# bt_rc_car_vehicle.net
KiCad netlist of a schematic drawn in EAGLE
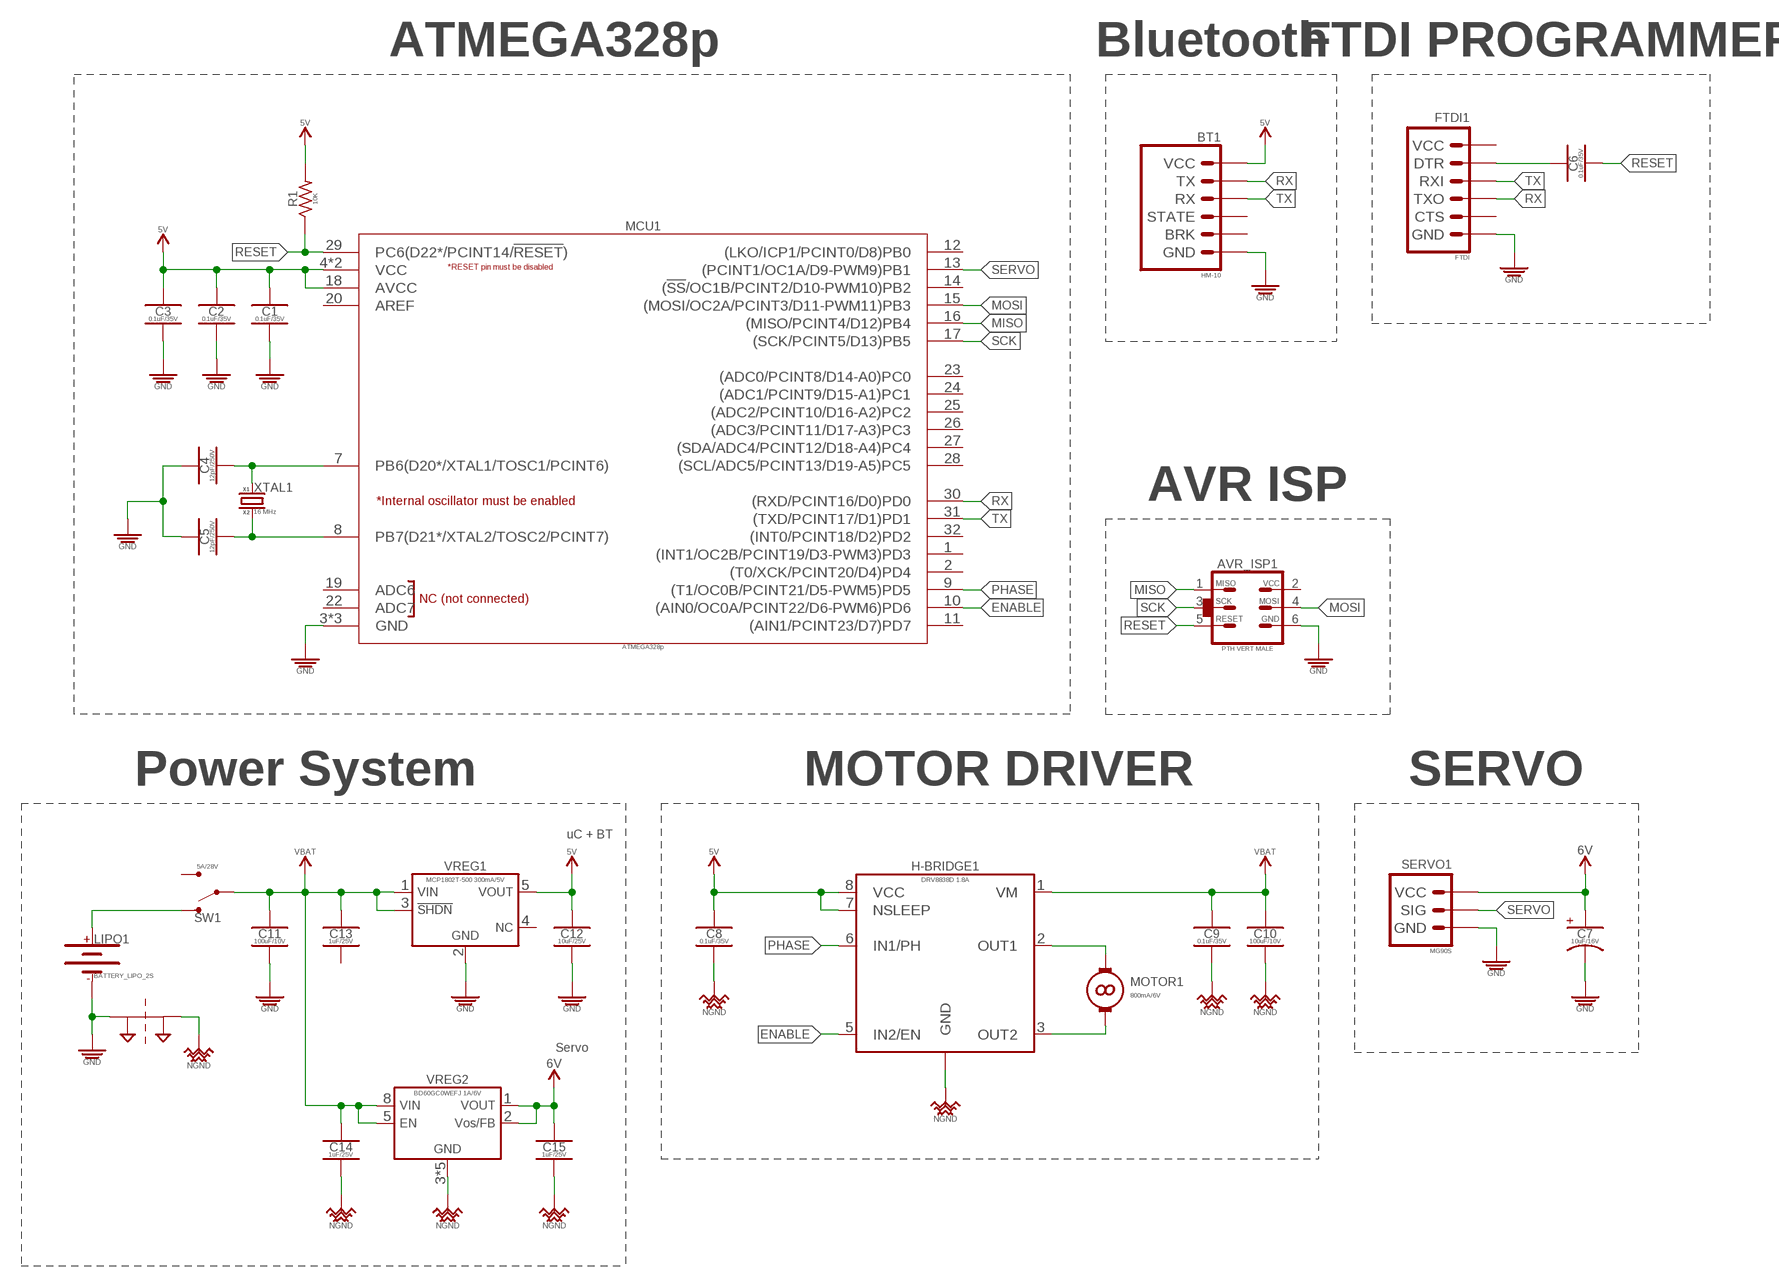
[diagram p0: schematic, sheet 1]

(export (version "E")
  (design (tool "Eeschema 10.0.6"))
  (components
    (comp (ref "AVR_ISP1")
      (value "PTH VERT MALE")
      (footprint "eagle-import:HDRV6W64P254_2X3_762X483X838B_AVR-ISP")
      (fields (field (name "MFR") "Amphenol FCI") (field (name "MPN") "67997-206HLF"))
      (libsource (lib "eagle-import") (part "AVR_SPI_PRG_6_PTH_VERT_MALE_2.54MM"))
    )
    (comp (ref "BT1")
      (value "HM-10")
      (footprint "eagle-import:HDRVR6W64P254_1X6_1574X254X850B")
      (fields (field (name "MFR") "JNHuaMao Technology Company"))
      (libsource (lib "eagle-import") (part "BLUETOOTH_HM-10_PTH_VERT_FEMALE_2.54MM"))
    )
    (comp (ref "C1")
      (value "0.1uF/35V")
      (footprint "eagle-import:CAPC2012X95_SMD-0805")
      (fields (field (name "MFR") "Taiyo Yuden") (field (name "MPN") "GMK212BJ104KGHT"))
      (libsource (lib "eagle-import") (part "0.1UF_SMD-0805_35V-10%"))
    )
    (comp (ref "C2")
      (value "0.1uF/35V")
      (footprint "eagle-import:CAPC2012X95_SMD-0805")
      (fields (field (name "MFR") "Taiyo Yuden") (field (name "MPN") "GMK212BJ104KGHT"))
      (libsource (lib "eagle-import") (part "0.1UF_SMD-0805_35V-10%"))
    )
    (comp (ref "C3")
      (value "0.1uF/35V")
      (footprint "eagle-import:CAPC2012X95_SMD-0805")
      (fields (field (name "MFR") "Taiyo Yuden") (field (name "MPN") "GMK212BJ104KGHT"))
      (libsource (lib "eagle-import") (part "0.1UF_SMD-0805_35V-10%"))
    )
    (comp (ref "C4")
      (value "12pF/250V")
      (footprint "eagle-import:CAPC2012X95_SMD-0805")
      (fields
        (field (name "MFR") "Murata Electronics North America")
        (field (name "MPN") "GRM21A5C2E120JW01D")
      )
      (libsource (lib "eagle-import") (part "12PF_SMD-0805_250V-5%"))
    )
    (comp (ref "C5")
      (value "12pF/250V")
      (footprint "eagle-import:CAPC2012X95_SMD-0805")
      (fields
        (field (name "MFR") "Murata Electronics North America")
        (field (name "MPN") "GRM21A5C2E120JW01D")
      )
      (libsource (lib "eagle-import") (part "12PF_SMD-0805_250V-5%"))
    )
    (comp (ref "C6")
      (value "0.1uF/35V")
      (footprint "eagle-import:CAPC2012X95_SMD-0805")
      (fields (field (name "MFR") "Taiyo Yuden") (field (name "MPN") "GMK212BJ104KGHT"))
      (libsource (lib "eagle-import") (part "0.1UF_SMD-0805_35V-10%"))
    )
    (comp (ref "C7")
      (value "10uF/16V")
      (footprint "eagle-import:CAPMP3216X180_SMD_CAP-TANT-1206")
      (fields (field (name "MFR") "TCJA106M016R0200"))
      (libsource (lib "eagle-import") (part "10UF-POLARIZED_SMD-1206_16V-20%_"))
    )
    (comp (ref "C8")
      (value "0.1uF/35V")
      (footprint "eagle-import:CAPC2012X95_SMD-0805")
      (fields (field (name "MFR") "Taiyo Yuden") (field (name "MPN") "GMK212BJ104KGHT"))
      (libsource (lib "eagle-import") (part "0.1UF_SMD-0805_35V-10%"))
    )
    (comp (ref "C9")
      (value "0.1uF/35V")
      (footprint "eagle-import:CAPC2012X95_SMD-0805")
      (fields (field (name "MFR") "Taiyo Yuden") (field (name "MPN") "GMK212BJ104KGHT"))
      (libsource (lib "eagle-import") (part "0.1UF_SMD-0805_35V-10%"))
    )
    (comp (ref "C10")
      (value "100uF/10V")
      (footprint "eagle-import:CAPC3225X270_SMD-1210")
      (fields (field (name "MFR") "Taiyo Yuden") (field (name "MPN") "LMK325ABJ107MMHT"))
      (libsource (lib "eagle-import") (part "100UF_CER_SMD-1210_16V-20%"))
    )
    (comp (ref "C11")
      (value "100uF/10V")
      (footprint "eagle-import:CAPC3225X270_SMD-1210")
      (fields (field (name "MFR") "Taiyo Yuden") (field (name "MPN") "LMK325ABJ107MMHT"))
      (libsource (lib "eagle-import") (part "100UF_CER_SMD-1210_16V-20%"))
    )
    (comp (ref "C12")
      (value "10uF/25V")
      (footprint "eagle-import:CAPC2012X95_SMD-0805")
      (fields
        (field (name "MFR") "Murata Electronics North America")
        (field (name "MPN") "GRM21BR61E106MA73L")
      )
      (libsource (lib "eagle-import") (part "10UF_CER_SMD-0805_25V-10%"))
    )
    (comp (ref "C13")
      (value "1uF/25V")
      (footprint "eagle-import:CAPC2012X95_SMD-0805")
      (fields (field (name "MFR") "KEMET") (field (name "MPN") "C0805C105K3RACTU"))
      (libsource (lib "eagle-import") (part "1UF_CER_SMD-0805_25V-10%"))
    )
    (comp (ref "C14")
      (value "1uF/25V")
      (footprint "eagle-import:CAPC2012X95_SMD-0805")
      (fields (field (name "MFR") "KEMET") (field (name "MPN") "C0805C105K3RACTU"))
      (libsource (lib "eagle-import") (part "1UF_CER_SMD-0805_25V-10%"))
    )
    (comp (ref "C15")
      (value "1uF/25V")
      (footprint "eagle-import:CAPC2012X95_SMD-0805")
      (fields (field (name "MFR") "KEMET") (field (name "MPN") "C0805C105K3RACTU"))
      (libsource (lib "eagle-import") (part "1UF_CER_SMD-0805_25V-10%"))
    )
    (comp (ref "FTDI1")
      (value "FTDI")
      (footprint "eagle-import:HDRV6W64P254_1X6_1524X254X838B_FTDI")
      (fields (field (name "MFR") "SparkFun Electronics") (field (name "MPN") "DEV-09873"))
      (libsource (lib "eagle-import") (part "FTDI_PTH_VERT_MALE_2.54MM"))
    )
    (comp (ref "H-BRIDGE1")
      (value "DRV8838D 1.8A")
      (footprint "eagle-import:WSON-8-PPAD")
      (fields (field (name "MFR") "Texas Instruments") (field (name "MPN") "DRV8838DSGR"))
      (libsource (lib "eagle-import") (part "DRV883X_H-BRIDGE_DRV8838D_1.8A"))
    )
    (comp (ref "LIPO1")
      (value "BATTERY_LIPO_2S")
      (footprint "eagle-import:DUAL_PTH_PADS")
      (libsource (lib "eagle-import") (part "BATTERY_LIPO_2S"))
    )
    (comp (ref "MCU1")
      (value "ATMEGA328p")
      (footprint "eagle-import:QFP80P900X900X120-32")
      (fields (field (name "MFR") "Microchip Technology") (field (name "MPN") "ATMEGA328P-AU"))
      (libsource (lib "eagle-import") (part "ATMEGA328P-32_TQFP-32_ATMEGA328P"))
    )
    (comp (ref "MOTOR1")
      (value "800mA/6V")
      (footprint "eagle-import:CONNECTOR_MOTOR")
      (fields (field (name "MFR") "Pololu") (field (name "MPN") "1117"))
      (libsource (lib "eagle-import") (part "MOTOR_SIZE-130"))
    )
    (comp (ref "NET_BRIDGE1")
      (value "NET_BRIDGE")
      (footprint "eagle-import:NET_BRIDGE")
      (libsource (lib "eagle-import") (part "NET_BRIDGE"))
    )
    (comp (ref "R1")
      (value "10K")
      (footprint "eagle-import:RESC2012X60_SMD-0805")
      (fields (field (name "MFR") "Yageo") (field (name "MPN") "RC0805JR-0710KL"))
      (libsource (lib "eagle-import") (part "10KΩ_SMD-0805_1/8W-5%"))
    )
    (comp (ref "SERVO1")
      (value "MG90S")
      (footprint "eagle-import:HDRV3W64P254_1X3_762X254X838B")
      (fields (field (name "MFR") "TowerPro"))
      (libsource (lib "eagle-import") (part "SERVO_MG90S_PTH_VERT_MALE_2.54MM"))
    )
    (comp (ref "SW1")
      (value "5A/28V")
      (footprint "eagle-import:SW_TOGGLE_SPDT_5A-28V_13L-7W")
      (fields (field (name "MFR") "E-Switch") (field (name "MPN") "100SP1T1B4M2QE"))
      (libsource (lib "eagle-import") (part "SWITCH_SPDT_VERT_PTH_5A-28V_13L-7W_"))
    )
    (comp (ref "VREG1")
      (value "MCP1802T-500 300mA/5V")
      (footprint "eagle-import:SOT95P280X145-5")
      (fields (field (name "MFR") "Microchip Technology") (field (name "MPN") "MCP1802T-5002I/OT"))
      (libsource (lib "eagle-import") (part "MCP18XX_MCP1802-500_300MA-5V"))
    )
    (comp (ref "VREG2")
      (value "BD60GC0WEFJ 1A/6V")
      (footprint "eagle-import:SOIC127P600X100-8")
      (fields (field (name "MFR") "Rohm Semiconductor") (field (name "MPN") "BD60GC0WEFJ-E2"))
      (libsource (lib "eagle-import") (part "BDXXGC0WEFJ_BD60GC0WEFJ_1A-6V"))
    )
    (comp (ref "XTAL1")
      (value "16 MHz")
      (footprint "eagle-import:OSCCC500X320X110_CRYSTAL")
      (fields (field (name "MFR") "Abracon LLC") (field (name "MPN") "ABM3B-16.000MHZ-B2-T"))
      (libsource (lib "eagle-import") (part "CRYSTAL_ABM3B_16MHZ_18PF"))
    )
  )
  (nets
    (net (code "1") (name "5V") (class "Default")
      (node (ref "BT1") (pin "VCC") (pinfunction "VCC_VCC") (pintype "passive"))
      (node (ref "C1") (pin "1") (pinfunction "1_1") (pintype "passive"))
      (node (ref "C12") (pin "1") (pinfunction "1_1") (pintype "passive"))
      (node (ref "C2") (pin "1") (pinfunction "1_1") (pintype "passive"))
      (node (ref "C3") (pin "1") (pinfunction "1_1") (pintype "passive"))
      (node (ref "C8") (pin "1") (pinfunction "1_1") (pintype "passive"))
      (node (ref "H-BRIDGE1") (pin "7") (pinfunction "NSLEEP_7") (pintype "passive"))
      (node (ref "H-BRIDGE1") (pin "8") (pinfunction "VCC_8") (pintype "passive"))
      (node (ref "MCU1") (pin "18") (pinfunction "AVCC_18") (pintype "power_in"))
      (node (ref "MCU1") (pin "4") (pinfunction "VCC_4") (pintype "power_in"))
      (node (ref "MCU1") (pin "6") (pinfunction "VCC_6") (pintype "power_in"))
      (node (ref "R1") (pin "2") (pinfunction "2_2") (pintype "passive"))
      (node (ref "VREG1") (pin "5") (pinfunction "VOUT_5") (pintype "passive"))
    )
    (net (code "2") (name "6V") (class "Default")
      (node (ref "C15") (pin "1") (pinfunction "1_1") (pintype "passive"))
      (node (ref "C7") (pin "A") (pinfunction "A_A") (pintype "passive"))
      (node (ref "SERVO1") (pin "VCC") (pinfunction "VCC_VCC") (pintype "passive"))
      (node (ref "VREG2") (pin "1") (pinfunction "VOUT_1") (pintype "bidirectional"))
      (node (ref "VREG2") (pin "2") (pinfunction "VOS/FB_2") (pintype "bidirectional"))
    )
    (net (code "3") (name "ENABLE") (class "Default")
      (node (ref "H-BRIDGE1") (pin "5") (pinfunction "IN2/EN_5") (pintype "input"))
      (node (ref "MCU1") (pin "10") (pinfunction "(AIN0/OC0A/PCINT22/D6-PWM6)PD6_10") (pintype "bidirectional"))
    )
    (net (code "4") (name "GND") (class "Default")
      (node (ref "AVR_ISP1") (pin "GND") (pinfunction "GND_GND") (pintype "power_in"))
      (node (ref "BT1") (pin "GND") (pinfunction "GND_GND") (pintype "passive"))
      (node (ref "C1") (pin "2") (pinfunction "2_2") (pintype "passive"))
      (node (ref "C11") (pin "2") (pinfunction "2_2") (pintype "passive"))
      (node (ref "C12") (pin "2") (pinfunction "2_2") (pintype "passive"))
      (node (ref "C2") (pin "2") (pinfunction "2_2") (pintype "passive"))
      (node (ref "C3") (pin "2") (pinfunction "2_2") (pintype "passive"))
      (node (ref "C4") (pin "1") (pinfunction "1_1") (pintype "passive"))
      (node (ref "C5") (pin "1") (pinfunction "1_1") (pintype "passive"))
      (node (ref "C7") (pin "K") (pinfunction "K_K") (pintype "passive"))
      (node (ref "FTDI1") (pin "GND") (pinfunction "GND_GND") (pintype "power_in"))
      (node (ref "LIPO1") (pin "-") (pinfunction "-_-") (pintype "power_in"))
      (node (ref "MCU1") (pin "21") (pinfunction "GND_21") (pintype "power_in"))
      (node (ref "MCU1") (pin "3") (pinfunction "GND_3") (pintype "power_in"))
      (node (ref "MCU1") (pin "5") (pinfunction "GND_5") (pintype "power_in"))
      (node (ref "NET_BRIDGE1") (pin "P$1") (pinfunction "P$1_P$1") (pintype "passive"))
      (node (ref "SERVO1") (pin "GND") (pinfunction "GND_GND") (pintype "passive"))
      (node (ref "VREG1") (pin "2") (pinfunction "GND_2") (pintype "passive"))
    )
    (net (code "5") (name "MISO") (class "Default")
      (node (ref "AVR_ISP1") (pin "MISO") (pinfunction "MISO_MISO") (pintype "bidirectional"))
      (node (ref "MCU1") (pin "16") (pinfunction "(MISO/PCINT4/D12)PB4_16") (pintype "bidirectional"))
    )
    (net (code "6") (name "MOSI") (class "Default")
      (node (ref "AVR_ISP1") (pin "MOSI") (pinfunction "MOSI_MOSI") (pintype "bidirectional"))
      (node (ref "MCU1") (pin "15") (pinfunction "(MOSI/OC2A/PCINT3/D11-PWM11)PB3_15") (pintype "bidirectional"))
    )
    (net (code "7") (name "NGND") (class "Default")
      (node (ref "C10") (pin "2") (pinfunction "2_2") (pintype "passive"))
      (node (ref "C14") (pin "2") (pinfunction "2_2") (pintype "passive"))
      (node (ref "C15") (pin "2") (pinfunction "2_2") (pintype "passive"))
      (node (ref "C8") (pin "2") (pinfunction "2_2") (pintype "passive"))
      (node (ref "C9") (pin "2") (pinfunction "2_2") (pintype "passive"))
      (node (ref "H-BRIDGE1") (pin "4") (pinfunction "GND_4") (pintype "passive"))
      (node (ref "H-BRIDGE1") (pin "GND") (pinfunction "GND_GND") (pintype "passive"))
      (node (ref "H-BRIDGE1") (pin "P$1") (pinfunction "GND_P$1") (pintype "passive"))
      (node (ref "H-BRIDGE1") (pin "P$2") (pinfunction "GND_P$2") (pintype "passive"))
      (node (ref "NET_BRIDGE1") (pin "P$2") (pinfunction "P$2_P$2") (pintype "passive"))
      (node (ref "VREG2") (pin "3") (pinfunction "GND_3") (pintype "bidirectional"))
      (node (ref "VREG2") (pin "4") (pinfunction "GND_4") (pintype "bidirectional"))
      (node (ref "VREG2") (pin "6") (pinfunction "GND_6") (pintype "bidirectional"))
      (node (ref "VREG2") (pin "7") (pinfunction "GND_7") (pintype "bidirectional"))
      (node (ref "VREG2") (pin "FIN") (pinfunction "GND_FIN") (pintype "bidirectional"))
    )
    (net (code "8") (name "Net-(C6-Pad1)") (class "Default")
      (node (ref "C6") (pin "1") (pinfunction "1_1") (pintype "passive"))
      (node (ref "FTDI1") (pin "DTR") (pinfunction "DTR_DTR") (pintype "bidirectional"))
    )
    (net (code "9") (name "Net-(H-BRIDGE1-OUT1)") (class "Default")
      (node (ref "H-BRIDGE1") (pin "2") (pinfunction "OUT1_2") (pintype "passive"))
      (node (ref "MOTOR1") (pin "+") (pinfunction "+_+") (pintype "passive"))
    )
    (net (code "10") (name "Net-(H-BRIDGE1-OUT2)") (class "Default")
      (node (ref "H-BRIDGE1") (pin "3") (pinfunction "OUT2_3") (pintype "passive"))
      (node (ref "MOTOR1") (pin "-") (pinfunction "-_-") (pintype "passive"))
    )
    (net (code "11") (name "Net-(LIPO1-Pad+)") (class "Default")
      (node (ref "LIPO1") (pin "+") (pinfunction "+_+") (pintype "power_in"))
      (node (ref "SW1") (pin "S1") (pinfunction "S1_S1") (pintype "passive"))
    )
    (net (code "12") (name "Net-(MCU1-PB6(D20*{slash}XTAL1{slash}TOSC1{slash}PCINT6))") (class "Default")
      (node (ref "C4") (pin "2") (pinfunction "2_2") (pintype "passive"))
      (node (ref "MCU1") (pin "7") (pinfunction "PB6(D20*/XTAL1/TOSC1/PCINT6)_7") (pintype "bidirectional"))
      (node (ref "XTAL1") (pin "1") (pinfunction "XTAL1_1") (pintype "passive"))
    )
    (net (code "13") (name "Net-(MCU1-PB7(D21*{slash}XTAL2{slash}TOSC2{slash}PCINT7))") (class "Default")
      (node (ref "C5") (pin "2") (pinfunction "2_2") (pintype "passive"))
      (node (ref "MCU1") (pin "8") (pinfunction "PB7(D21*/XTAL2/TOSC2/PCINT7)_8") (pintype "bidirectional"))
      (node (ref "XTAL1") (pin "3") (pinfunction "XTAL2_3") (pintype "passive"))
    )
    (net (code "14") (name "PHASE") (class "Default")
      (node (ref "H-BRIDGE1") (pin "6") (pinfunction "IN1/PH_6") (pintype "input"))
      (node (ref "MCU1") (pin "9") (pinfunction "(T1/OC0B/PCINT21/D5-PWM5)PD5_9") (pintype "bidirectional"))
    )
    (net (code "15") (name "RESET") (class "Default")
      (node (ref "AVR_ISP1") (pin "RESET") (pinfunction "RESET_RESET") (pintype "bidirectional"))
      (node (ref "C6") (pin "2") (pinfunction "2_2") (pintype "passive"))
      (node (ref "MCU1") (pin "29") (pinfunction "PC6(D22*/PCINT14/~{RESET})_29") (pintype "bidirectional"))
      (node (ref "R1") (pin "1") (pinfunction "1_1") (pintype "passive"))
    )
    (net (code "16") (name "RX") (class "Default")
      (node (ref "BT1") (pin "TX") (pinfunction "TX_TX") (pintype "output"))
      (node (ref "FTDI1") (pin "TX") (pinfunction "TXO_TX") (pintype "output"))
      (node (ref "MCU1") (pin "30") (pinfunction "(RXD/PCINT16/D0)PD0_30") (pintype "bidirectional"))
    )
    (net (code "17") (name "SCK") (class "Default")
      (node (ref "AVR_ISP1") (pin "SCK") (pinfunction "SCK_SCK") (pintype "bidirectional"))
      (node (ref "MCU1") (pin "17") (pinfunction "(SCK/PCINT5/D13)PB5_17") (pintype "bidirectional"))
    )
    (net (code "18") (name "SERVO") (class "Default")
      (node (ref "MCU1") (pin "13") (pinfunction "(PCINT1/OC1A/D9-PWM9)PB1_13") (pintype "bidirectional"))
      (node (ref "SERVO1") (pin "SIG") (pinfunction "SIG_SIG") (pintype "passive"))
    )
    (net (code "19") (name "TX") (class "Default")
      (node (ref "BT1") (pin "RX") (pinfunction "RX_RX") (pintype "input"))
      (node (ref "FTDI1") (pin "RX") (pinfunction "RXI_RX") (pintype "input"))
      (node (ref "MCU1") (pin "31") (pinfunction "(TXD/PCINT17/D1)PD1_31") (pintype "bidirectional"))
    )
    (net (code "20") (name "VBAT") (class "Default")
      (node (ref "C10") (pin "1") (pinfunction "1_1") (pintype "passive"))
      (node (ref "C11") (pin "1") (pinfunction "1_1") (pintype "passive"))
      (node (ref "C13") (pin "1") (pinfunction "1_1") (pintype "passive"))
      (node (ref "C14") (pin "1") (pinfunction "1_1") (pintype "passive"))
      (node (ref "C9") (pin "1") (pinfunction "1_1") (pintype "passive"))
      (node (ref "H-BRIDGE1") (pin "1") (pinfunction "VM_1") (pintype "passive"))
      (node (ref "SW1") (pin "P") (pinfunction "P_P") (pintype "passive"))
      (node (ref "VREG1") (pin "1") (pinfunction "VIN_1") (pintype "passive"))
      (node (ref "VREG1") (pin "3") (pinfunction "~{SHDN}_3") (pintype "passive"))
      (node (ref "VREG2") (pin "5") (pinfunction "EN_5") (pintype "bidirectional"))
      (node (ref "VREG2") (pin "8") (pinfunction "VIN_8") (pintype "bidirectional"))
    )
    (net (code "21") (name "unconnected-(AVR_ISP1-PadVCC)") (class "Default")
      (node (ref "AVR_ISP1") (pin "VCC") (pinfunction "VCC_VCC") (pintype "no_connect"))
    )
    (net (code "22") (name "unconnected-(BT1-PadBRK)") (class "Default")
      (node (ref "BT1") (pin "BRK") (pinfunction "BRK_BRK") (pintype "no_connect"))
    )
    (net (code "23") (name "unconnected-(BT1-PadSTATE)") (class "Default")
      (node (ref "BT1") (pin "STATE") (pinfunction "STATE_STATE") (pintype "no_connect"))
    )
    (net (code "24") (name "unconnected-(C13-Pad2)") (class "Default")
      (node (ref "C13") (pin "2") (pinfunction "2_2") (pintype "passive"))
    )
    (net (code "25") (name "unconnected-(FTDI1-PadCTS)") (class "Default")
      (node (ref "FTDI1") (pin "CTS") (pinfunction "CTS_CTS") (pintype "no_connect"))
    )
    (net (code "26") (name "unconnected-(FTDI1-PadVCC)") (class "Default")
      (node (ref "FTDI1") (pin "VCC") (pinfunction "VCC_VCC") (pintype "no_connect"))
    )
    (net (code "27") (name "unconnected-(MCU1-(ADC0{slash}PCINT8{slash}D14-A0)PC0-Pad23)") (class "Default")
      (node (ref "MCU1") (pin "23") (pinfunction "(ADC0/PCINT8/D14-A0)PC0_23") (pintype "bidirectional"))
    )
    (net (code "28") (name "unconnected-(MCU1-(ADC1{slash}PCINT9{slash}D15-A1)PC1-Pad24)") (class "Default")
      (node (ref "MCU1") (pin "24") (pinfunction "(ADC1/PCINT9/D15-A1)PC1_24") (pintype "bidirectional"))
    )
    (net (code "29") (name "unconnected-(MCU1-(ADC2{slash}PCINT10{slash}D16-A2)PC2-Pad25)") (class "Default")
      (node (ref "MCU1") (pin "25") (pinfunction "(ADC2/PCINT10/D16-A2)PC2_25") (pintype "bidirectional"))
    )
    (net (code "30") (name "unconnected-(MCU1-(ADC3{slash}PCINT11{slash}D17-A3)PC3-Pad26)") (class "Default")
      (node (ref "MCU1") (pin "26") (pinfunction "(ADC3/PCINT11/D17-A3)PC3_26") (pintype "bidirectional"))
    )
    (net (code "31") (name "unconnected-(MCU1-(AIN1{slash}PCINT23{slash}D7)PD7-Pad11)") (class "Default")
      (node (ref "MCU1") (pin "11") (pinfunction "(AIN1/PCINT23/D7)PD7_11") (pintype "bidirectional"))
    )
    (net (code "32") (name "unconnected-(MCU1-(INT0{slash}PCINT18{slash}D2)PD2-Pad32)") (class "Default")
      (node (ref "MCU1") (pin "32") (pinfunction "(INT0/PCINT18/D2)PD2_32") (pintype "bidirectional"))
    )
    (net (code "33") (name "unconnected-(MCU1-(INT1{slash}OC2B{slash}PCINT19{slash}D3-PWM3)PD3-Pad1)") (class "Default")
      (node (ref "MCU1") (pin "1") (pinfunction "(INT1/OC2B/PCINT19/D3-PWM3)PD3_1") (pintype "bidirectional"))
    )
    (net (code "34") (name "unconnected-(MCU1-(LKO{slash}ICP1{slash}PCINT0{slash}D8)PB0-Pad12)") (class "Default")
      (node (ref "MCU1") (pin "12") (pinfunction "(LKO/ICP1/PCINT0/D8)PB0_12") (pintype "bidirectional"))
    )
    (net (code "35") (name "unconnected-(MCU1-(SCL{slash}ADC5{slash}PCINT13{slash}D19-A5)PC5-Pad28)") (class "Default")
      (node (ref "MCU1") (pin "28") (pinfunction "(SCL/ADC5/PCINT13/D19-A5)PC5_28") (pintype "bidirectional"))
    )
    (net (code "36") (name "unconnected-(MCU1-(SDA{slash}ADC4{slash}PCINT12{slash}D18-A4)PC4-Pad27)") (class "Default")
      (node (ref "MCU1") (pin "27") (pinfunction "(SDA/ADC4/PCINT12/D18-A4)PC4_27") (pintype "bidirectional"))
    )
    (net (code "37") (name "unconnected-(MCU1-(T0{slash}XCK{slash}PCINT20{slash}D4)PD4-Pad2)") (class "Default")
      (node (ref "MCU1") (pin "2") (pinfunction "(T0/XCK/PCINT20/D4)PD4_2") (pintype "bidirectional"))
    )
    (net (code "38") (name "unconnected-(MCU1-(~{SS}{slash}OC1B{slash}PCINT2{slash}D10-PWM10)PB2-Pad14)") (class "Default")
      (node (ref "MCU1") (pin "14") (pinfunction "(~{SS}/OC1B/PCINT2/D10-PWM10)PB2_14") (pintype "bidirectional"))
    )
    (net (code "39") (name "unconnected-(MCU1-ADC6-Pad19)") (class "Default")
      (node (ref "MCU1") (pin "19") (pinfunction "ADC6_19") (pintype "no_connect"))
    )
    (net (code "40") (name "unconnected-(MCU1-ADC7-Pad22)") (class "Default")
      (node (ref "MCU1") (pin "22") (pinfunction "ADC7_22") (pintype "no_connect"))
    )
    (net (code "41") (name "unconnected-(MCU1-AREF-Pad20)") (class "Default")
      (node (ref "MCU1") (pin "20") (pinfunction "AREF_20") (pintype "passive"))
    )
    (net (code "42") (name "unconnected-(SW1-PadS2)") (class "Default")
      (node (ref "SW1") (pin "S2") (pinfunction "S2_S2") (pintype "passive"))
    )
    (net (code "43") (name "unconnected-(VREG1-NC-Pad4)") (class "Default")
      (node (ref "VREG1") (pin "4") (pinfunction "NC_4") (pintype "passive"))
    )
  )
)
